# TRSW_and_RXamp_FINAL_mods.net
KiCad netlist of a schematic drawn in EAGLE
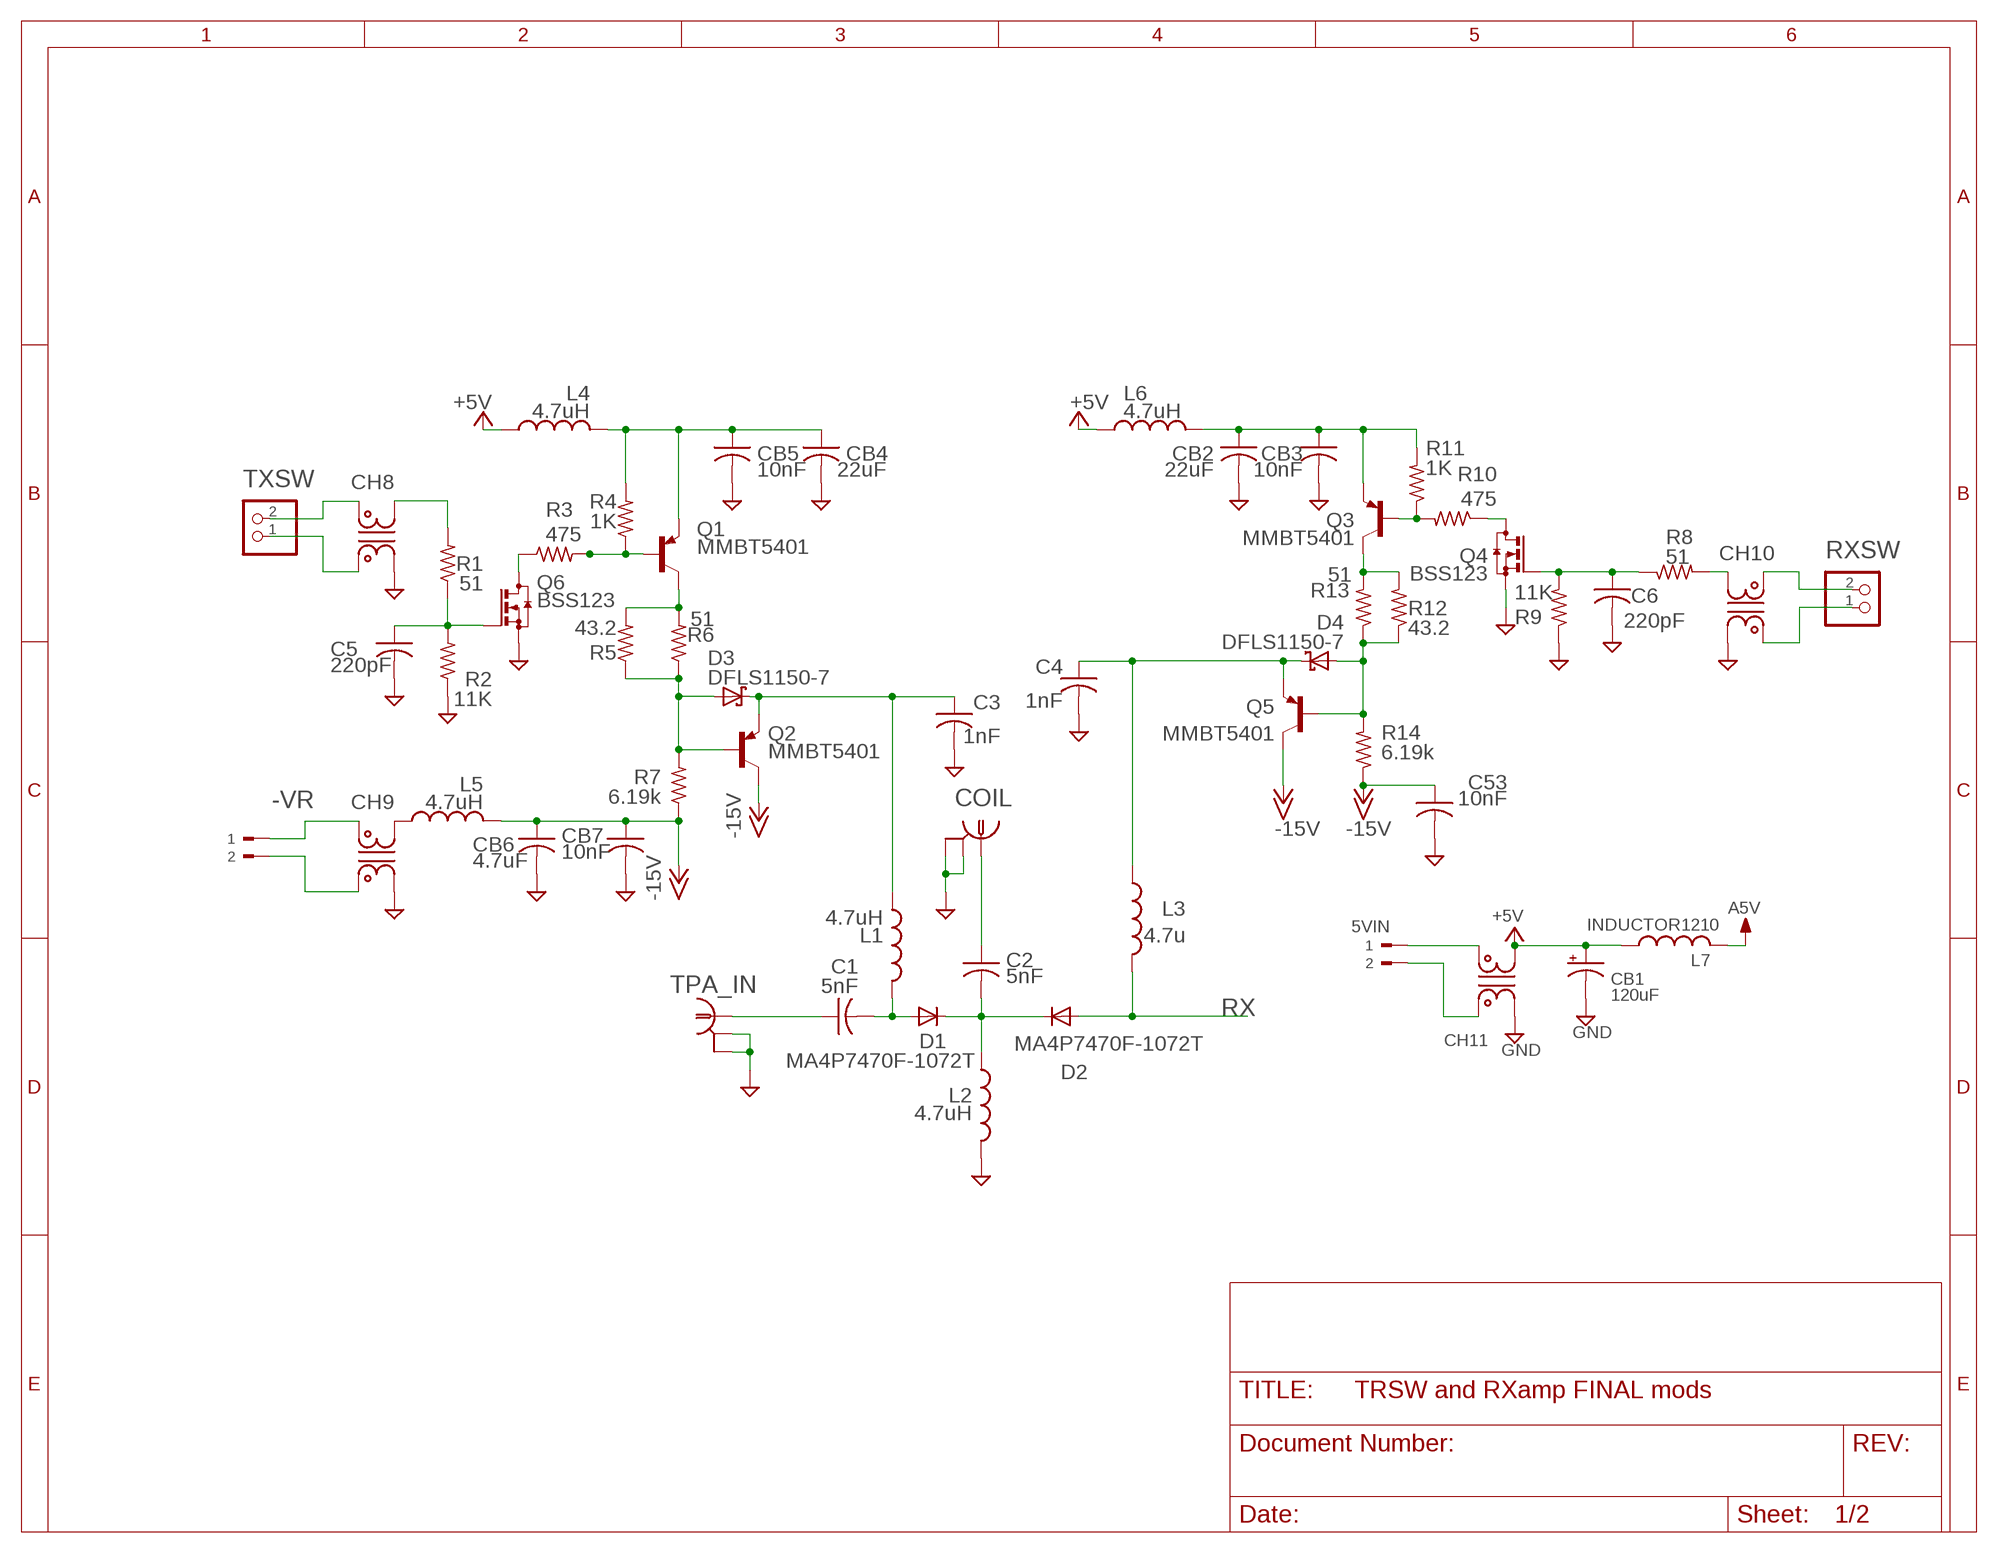
[diagram p0: schematic, sheet 1]
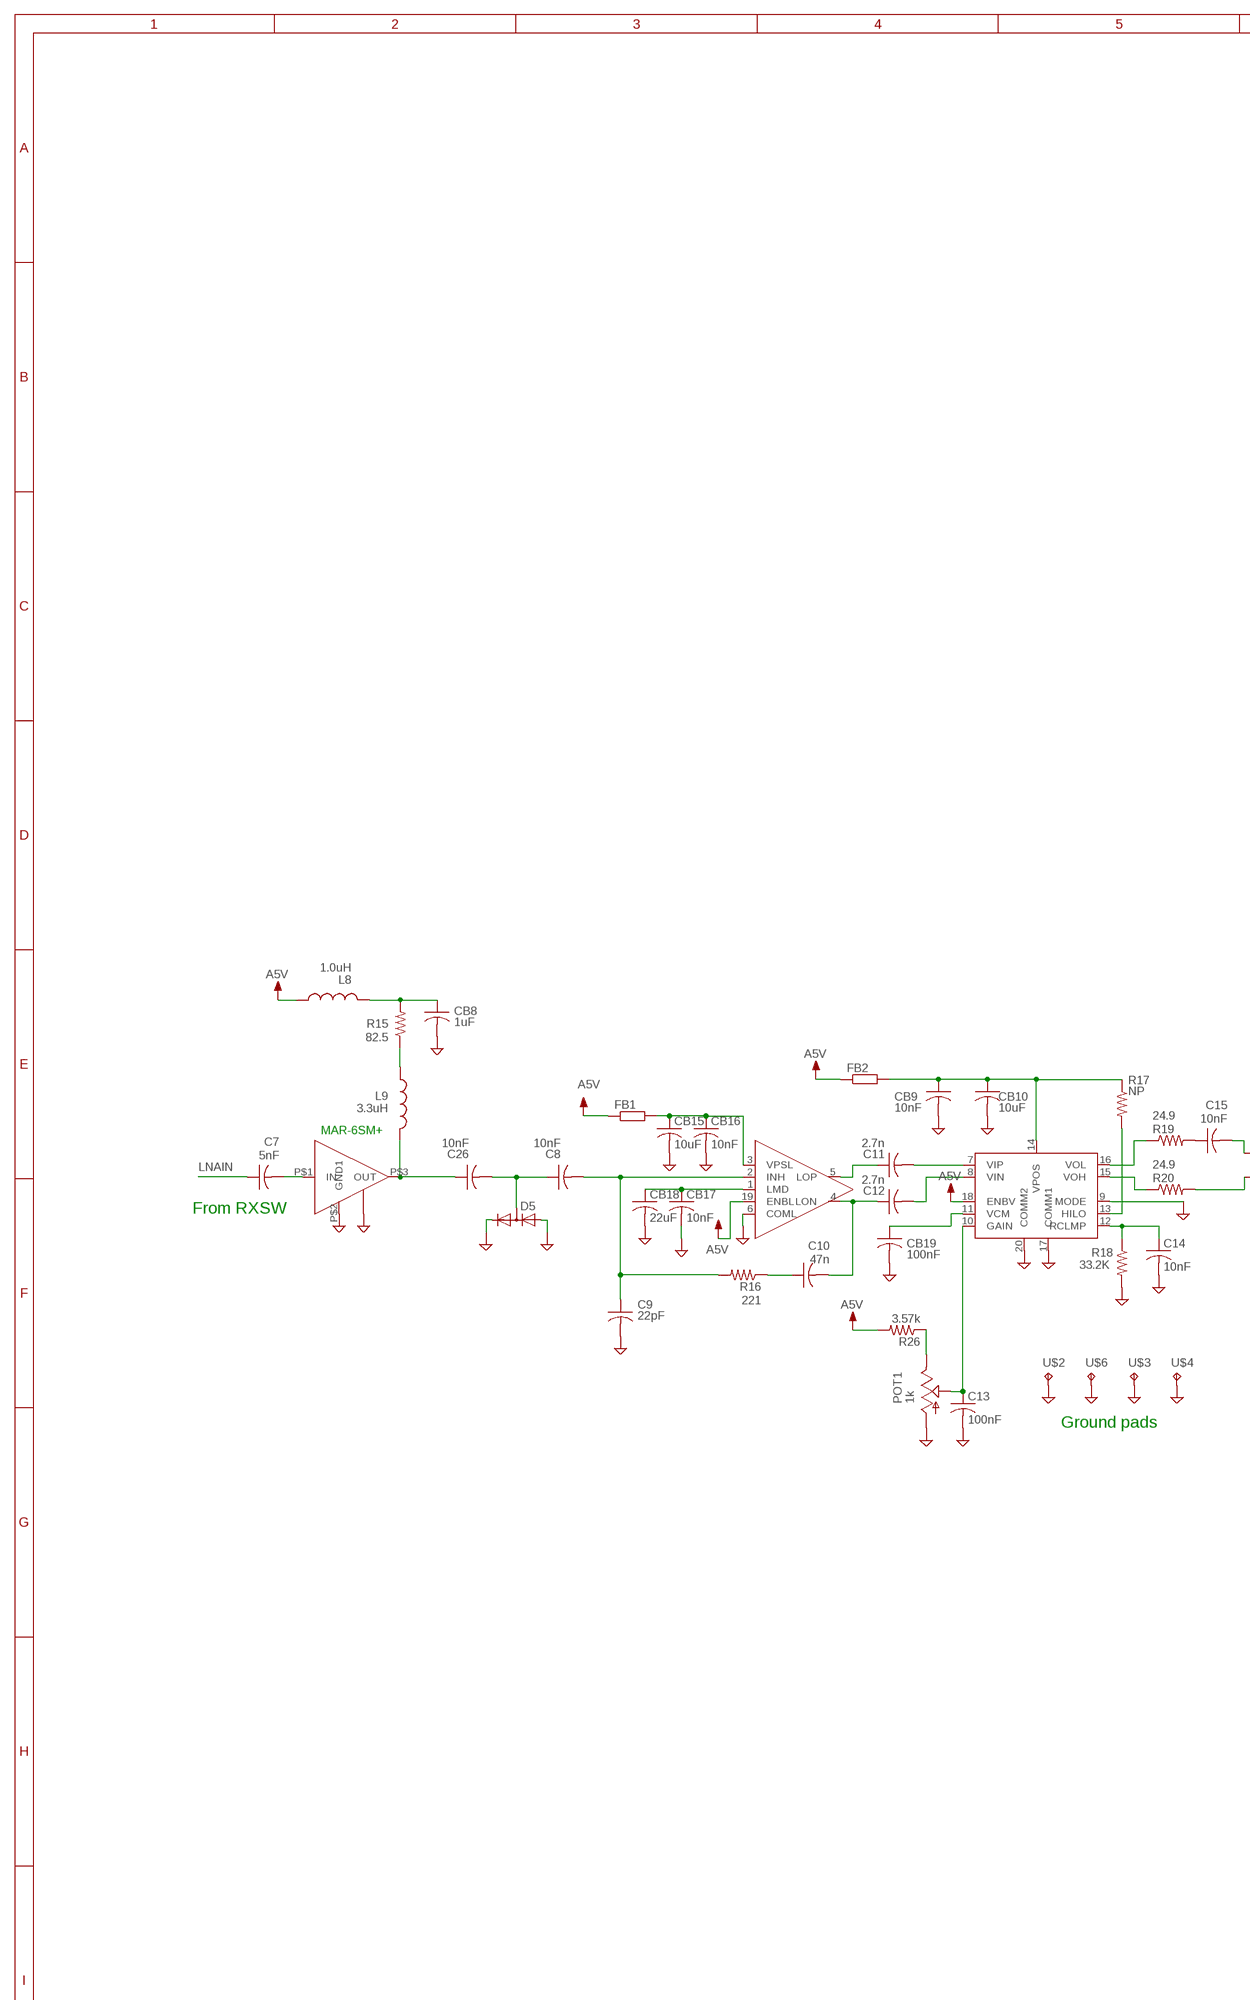
[diagram p1: schematic, sheet 2, part 1 of 2]
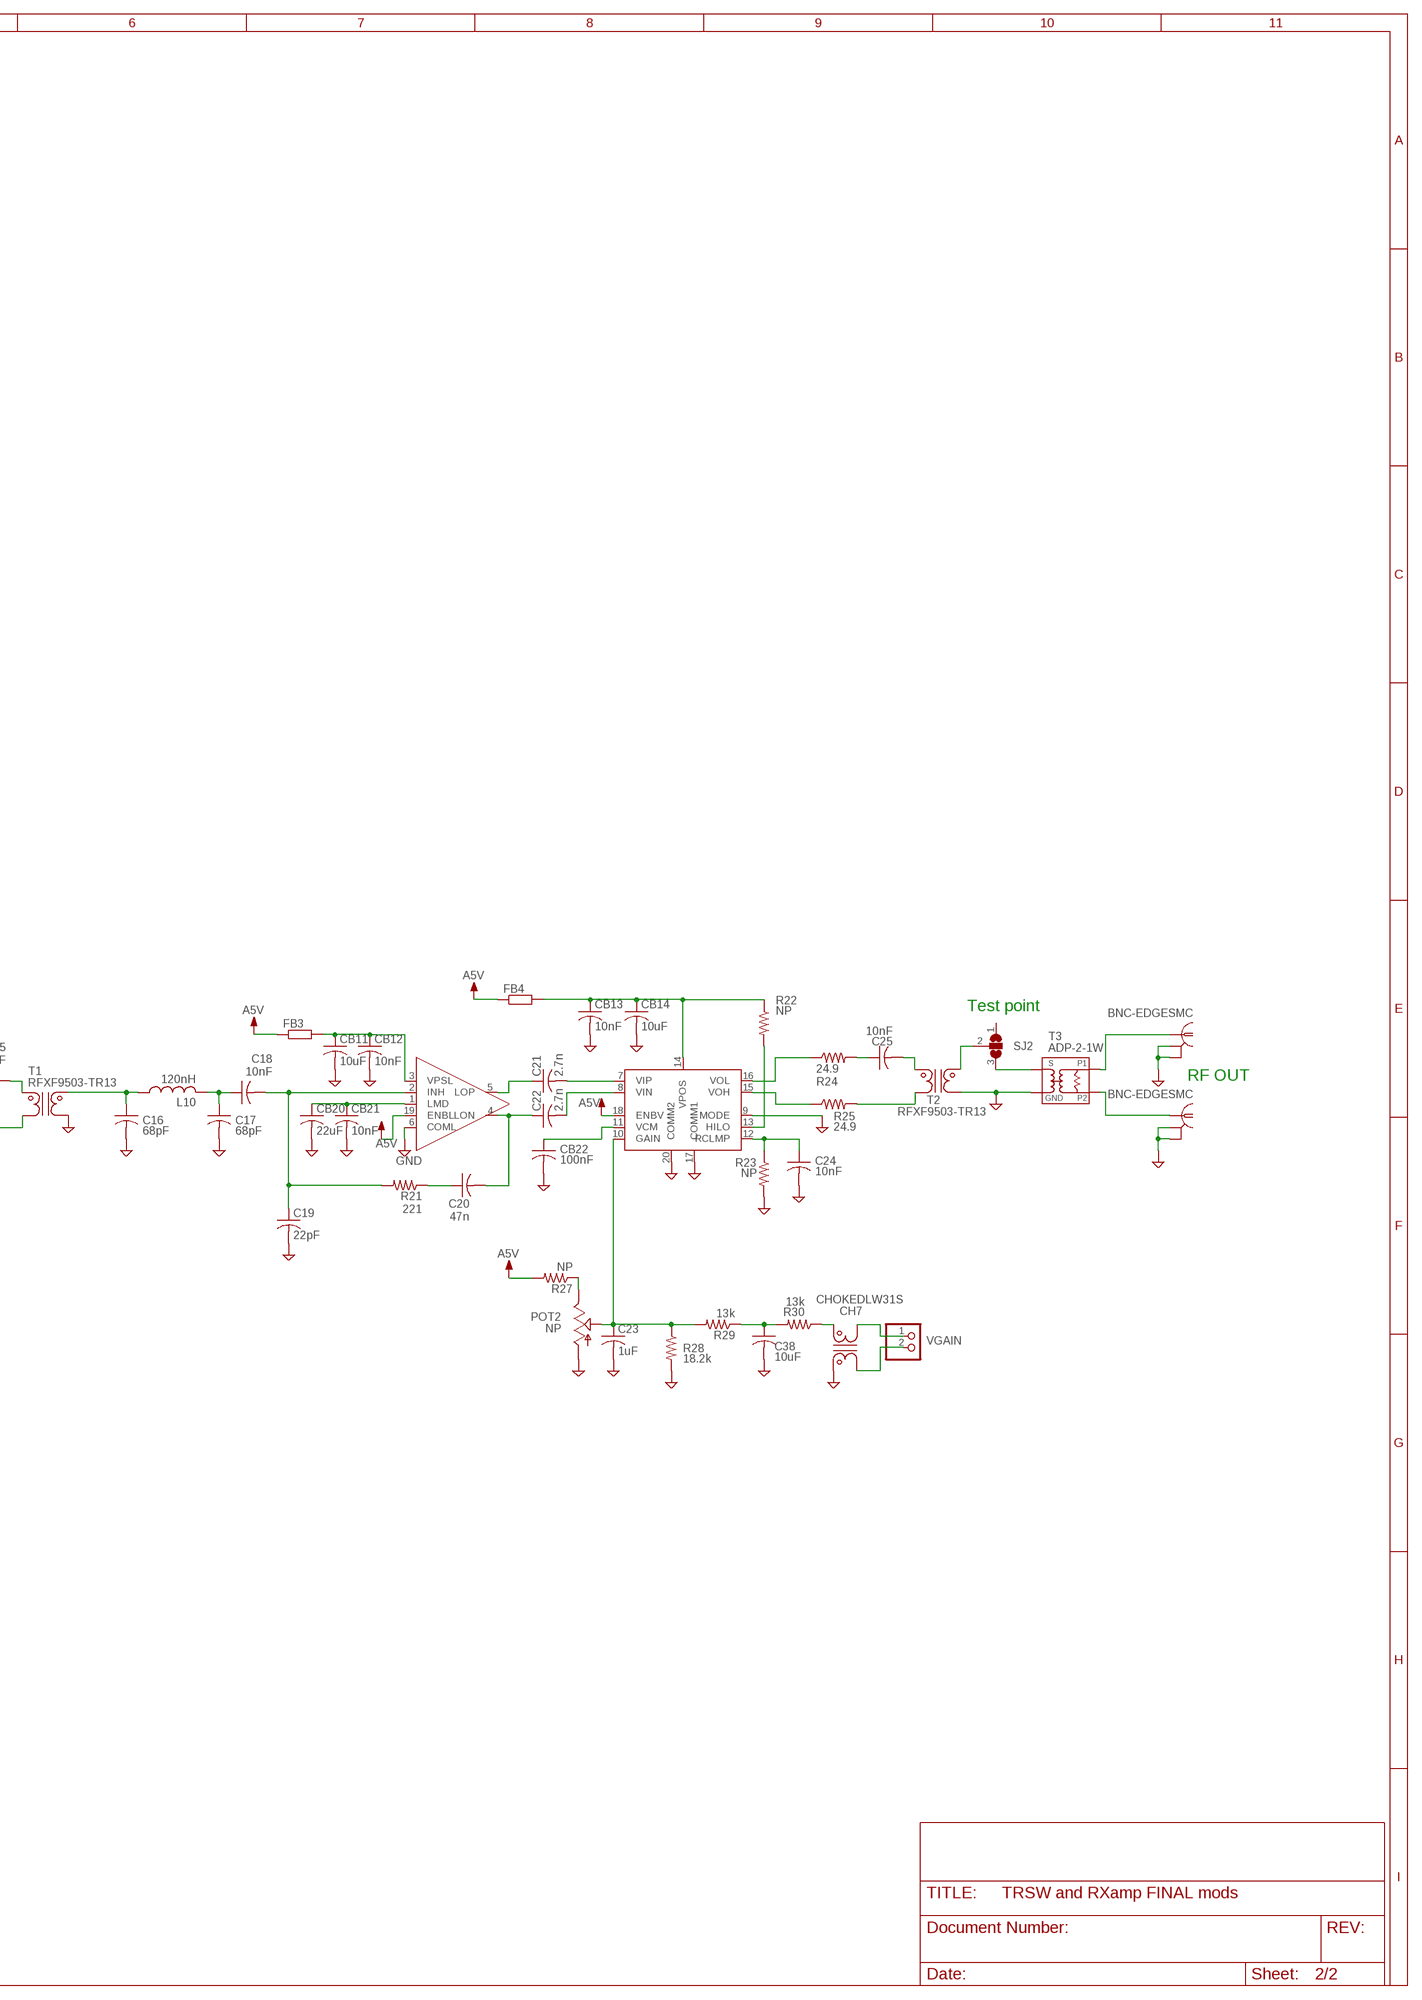
[diagram p2: schematic, sheet 2, part 2 of 2]

(export (version "E")
  (design (tool "Eeschema 10.0.6"))
  (components
    (comp (ref "C7")
      (value "5nF")
      (footprint "eagle-import:1008")
      (libsource (lib "eagle-import") (part "CAPACITOR1008"))
    )
    (comp (ref "C8")
      (value "10nF")
      (footprint "eagle-import:C0805")
      (libsource (lib "eagle-import") (part "C-USC0805"))
    )
    (comp (ref "C9")
      (value "22pF")
      (footprint "eagle-import:C0805")
      (libsource (lib "eagle-import") (part "C-USC0805"))
    )
    (comp (ref "C10")
      (value "47n")
      (footprint "eagle-import:C0805")
      (libsource (lib "eagle-import") (part "C-USC0805"))
    )
    (comp (ref "C11")
      (value "2.7n")
      (footprint "eagle-import:C0603")
      (libsource (lib "eagle-import") (part "C-USC0603"))
    )
    (comp (ref "C12")
      (value "2.7n")
      (footprint "eagle-import:C0603")
      (libsource (lib "eagle-import") (part "C-USC0603"))
    )
    (comp (ref "C13")
      (value "100nF")
      (footprint "eagle-import:C0603")
      (libsource (lib "eagle-import") (part "C-USC0603"))
    )
    (comp (ref "C14")
      (value "10nF")
      (footprint "eagle-import:C0603")
      (libsource (lib "eagle-import") (part "C-USC0603"))
    )
    (comp (ref "C15")
      (value "10nF")
      (footprint "eagle-import:C0603")
      (libsource (lib "eagle-import") (part "C-USC0603"))
    )
    (comp (ref "C16")
      (value "68pF")
      (footprint "eagle-import:1008")
      (libsource (lib "eagle-import") (part "CAPACITOR1008"))
    )
    (comp (ref "C17")
      (value "68pF")
      (footprint "eagle-import:1008")
      (libsource (lib "eagle-import") (part "CAPACITOR1008"))
    )
    (comp (ref "C18")
      (value "10nF")
      (footprint "eagle-import:C0805")
      (libsource (lib "eagle-import") (part "C-USC0805"))
    )
    (comp (ref "C19")
      (value "22pF")
      (footprint "eagle-import:C0805")
      (libsource (lib "eagle-import") (part "C-USC0805"))
    )
    (comp (ref "C20")
      (value "47n")
      (footprint "eagle-import:C0805")
      (libsource (lib "eagle-import") (part "C-USC0805"))
    )
    (comp (ref "C21")
      (value "2.7n")
      (footprint "eagle-import:C0603")
      (libsource (lib "eagle-import") (part "C-USC0603"))
    )
    (comp (ref "C22")
      (value "2.7n")
      (footprint "eagle-import:C0603")
      (libsource (lib "eagle-import") (part "C-USC0603"))
    )
    (comp (ref "C23")
      (value "1uF")
      (footprint "eagle-import:C0805")
      (libsource (lib "eagle-import") (part "C-USC0805"))
    )
    (comp (ref "C24")
      (value "10nF")
      (footprint "eagle-import:C0603")
      (libsource (lib "eagle-import") (part "C-USC0603"))
    )
    (comp (ref "C25")
      (value "10nF")
      (footprint "eagle-import:C0603")
      (libsource (lib "eagle-import") (part "C-USC0603"))
    )
    (comp (ref "C26")
      (value "10nF")
      (footprint "eagle-import:C0805")
      (libsource (lib "eagle-import") (part "C-USC0805"))
    )
    (comp (ref "C38")
      (value "10uF")
      (footprint "eagle-import:C0805")
      (libsource (lib "eagle-import") (part "C-USC0805"))
    )
    (comp (ref "CB8")
      (value "1uF")
      (footprint "eagle-import:C0805")
      (libsource (lib "eagle-import") (part "C-USC0805"))
    )
    (comp (ref "CB9")
      (value "10nF")
      (footprint "eagle-import:C0603")
      (libsource (lib "eagle-import") (part "C-USC0603"))
    )
    (comp (ref "CB10")
      (value "10uF")
      (footprint "eagle-import:C0805")
      (libsource (lib "eagle-import") (part "C-USC0805"))
    )
    (comp (ref "CB11")
      (value "10uF")
      (footprint "eagle-import:C0805")
      (libsource (lib "eagle-import") (part "C-USC0805"))
    )
    (comp (ref "CB12")
      (value "10nF")
      (footprint "eagle-import:C0603")
      (libsource (lib "eagle-import") (part "C-USC0603"))
    )
    (comp (ref "CB13")
      (value "10nF")
      (footprint "eagle-import:C0603")
      (libsource (lib "eagle-import") (part "C-USC0603"))
    )
    (comp (ref "CB14")
      (value "10uF")
      (footprint "eagle-import:C0805")
      (libsource (lib "eagle-import") (part "C-USC0805"))
    )
    (comp (ref "CB15")
      (value "10uF")
      (footprint "eagle-import:C0805")
      (libsource (lib "eagle-import") (part "C-USC0805"))
    )
    (comp (ref "CB16")
      (value "10nF")
      (footprint "eagle-import:C0603")
      (libsource (lib "eagle-import") (part "C-USC0603"))
    )
    (comp (ref "CB17")
      (value "10nF")
      (footprint "eagle-import:C0603")
      (libsource (lib "eagle-import") (part "C-USC0603"))
    )
    (comp (ref "CB18")
      (value "22uF")
      (footprint "eagle-import:C0805")
      (libsource (lib "eagle-import") (part "C-USC0805"))
    )
    (comp (ref "CB19")
      (value "100nF")
      (footprint "eagle-import:C0603")
      (libsource (lib "eagle-import") (part "C-USC0603"))
    )
    (comp (ref "CB20")
      (value "22uF")
      (footprint "eagle-import:C0805")
      (libsource (lib "eagle-import") (part "C-USC0805"))
    )
    (comp (ref "CB21")
      (value "10nF")
      (footprint "eagle-import:C0603")
      (libsource (lib "eagle-import") (part "C-USC0603"))
    )
    (comp (ref "CB22")
      (value "100nF")
      (footprint "eagle-import:C0603")
      (libsource (lib "eagle-import") (part "C-USC0603"))
    )
    (comp (ref "CH7")
      (value "CHOKEDLW31S")
      (footprint "eagle-import:CHOKE_DLW31S")
      (libsource (lib "eagle-import") (part "CHOKEDLW31S"))
    )
    (comp (ref "D5")
      (value "DIODE_2CACA-SOT23")
      (footprint "eagle-import:SOT23")
      (libsource (lib "eagle-import") (part "DIODE_2CACA-SOT23"))
    )
    (comp (ref "FB1")
      (value "R-EU_R0603")
      (footprint "eagle-import:R0603")
      (libsource (lib "eagle-import") (part "R-EU_R0603"))
    )
    (comp (ref "FB2")
      (value "R-EU_R0603")
      (footprint "eagle-import:R0603")
      (libsource (lib "eagle-import") (part "R-EU_R0603"))
    )
    (comp (ref "FB3")
      (value "R-EU_R0603")
      (footprint "eagle-import:R0603")
      (libsource (lib "eagle-import") (part "R-EU_R0603"))
    )
    (comp (ref "FB4")
      (value "R-EU_R0603")
      (footprint "eagle-import:R0603")
      (libsource (lib "eagle-import") (part "R-EU_R0603"))
    )
    (comp (ref "L8")
      (value "1.0uH")
      (footprint "eagle-import:1008")
      (libsource (lib "eagle-import") (part "INDUCTOR1008"))
    )
    (comp (ref "L9")
      (value "3.3uH")
      (footprint "eagle-import:1008")
      (libsource (lib "eagle-import") (part "INDUCTOR1008"))
    )
    (comp (ref "L10")
      (value "120nH")
      (footprint "eagle-import:1008")
      (libsource (lib "eagle-import") (part "INDUCTOR1008"))
    )
    (comp (ref "LNA")
      (value "MAR-6SM+")
      (footprint "eagle-import:WW107")
      (libsource (lib "eagle-import") (part "MAR-6SM+"))
    )
    (comp (ref "POT1")
      (value "1k")
      (footprint "eagle-import:3223W")
      (libsource (lib "eagle-import") (part "TRIM_US-3223W"))
    )
    (comp (ref "POT2")
      (value "NP")
      (footprint "eagle-import:3223W")
      (libsource (lib "eagle-import") (part "TRIM_US-3223W"))
    )
    (comp (ref "R15")
      (value "82.5")
      (footprint "eagle-import:R0805")
      (libsource (lib "eagle-import") (part "R-US_R0805"))
    )
    (comp (ref "R16")
      (value "221")
      (footprint "eagle-import:R0805")
      (libsource (lib "eagle-import") (part "R-US_R0805"))
    )
    (comp (ref "R17")
      (value "NP")
      (footprint "eagle-import:R0805")
      (libsource (lib "eagle-import") (part "R-US_R0805"))
    )
    (comp (ref "R18")
      (value "33.2K")
      (footprint "eagle-import:R0805")
      (libsource (lib "eagle-import") (part "R-US_R0805"))
    )
    (comp (ref "R19")
      (value "24.9")
      (footprint "eagle-import:R0805")
      (libsource (lib "eagle-import") (part "R-US_R0805"))
    )
    (comp (ref "R20")
      (value "24.9")
      (footprint "eagle-import:R0805")
      (libsource (lib "eagle-import") (part "R-US_R0805"))
    )
    (comp (ref "R21")
      (value "221")
      (footprint "eagle-import:R0805")
      (libsource (lib "eagle-import") (part "R-US_R0805"))
    )
    (comp (ref "R22")
      (value "NP")
      (footprint "eagle-import:R0805")
      (libsource (lib "eagle-import") (part "R-US_R0805"))
    )
    (comp (ref "R23")
      (value "NP")
      (footprint "eagle-import:R0805")
      (libsource (lib "eagle-import") (part "R-US_R0805"))
    )
    (comp (ref "R24")
      (value "24.9")
      (footprint "eagle-import:R0805")
      (libsource (lib "eagle-import") (part "R-US_R0805"))
    )
    (comp (ref "R25")
      (value "24.9")
      (footprint "eagle-import:R0805")
      (libsource (lib "eagle-import") (part "R-US_R0805"))
    )
    (comp (ref "R26")
      (value "3.57k")
      (footprint "eagle-import:R0805")
      (libsource (lib "eagle-import") (part "R-US_R0805"))
    )
    (comp (ref "R27")
      (value "NP")
      (footprint "eagle-import:R0805")
      (libsource (lib "eagle-import") (part "R-US_R0805"))
    )
    (comp (ref "R28")
      (value "18.2k")
      (footprint "eagle-import:R0805")
      (libsource (lib "eagle-import") (part "R-US_R0805"))
    )
    (comp (ref "R29")
      (value "13k")
      (footprint "eagle-import:R0805")
      (libsource (lib "eagle-import") (part "R-US_R0805"))
    )
    (comp (ref "R30")
      (value "13k")
      (footprint "eagle-import:R0805")
      (libsource (lib "eagle-import") (part "R-US_R0805"))
    )
    (comp (ref "RF_OUT")
      (value "BNC-EDGESMC")
      (footprint "eagle-import:SMC-EDGE")
      (libsource (lib "eagle-import") (part "BNC-EDGESMC"))
    )
    (comp (ref "SJ2")
      (value "SJ2W")
      (footprint "eagle-import:SJ_2")
      (libsource (lib "eagle-import") (part "SJ2W"))
    )
    (comp (ref "T1")
      (value "RFXF9503-TR13")
      (footprint "eagle-import:CX20XX_BALUN")
      (libsource (lib "eagle-import") (part "BALUN_1{colon}1"))
    )
    (comp (ref "T2")
      (value "RFXF9503-TR13")
      (footprint "eagle-import:CX20XX_BALUN")
      (libsource (lib "eagle-import") (part "BALUN_1{colon}1"))
    )
    (comp (ref "T3")
      (value "ADP-2-1W")
      (footprint "eagle-import:CD636")
      (libsource (lib "eagle-import") (part "ADP-2-1W"))
    )
    (comp (ref "U$2")
      (value "TESTPOINTKEYSTONE_ELECTRONICS_5016")
      (footprint "eagle-import:SMD_TESTPAD")
      (libsource (lib "eagle-import") (part "TESTPOINTKEYSTONE_ELECTRONICS_5016"))
    )
    (comp (ref "U$3")
      (value "TESTPOINTKEYSTONE_ELECTRONICS_5016")
      (footprint "eagle-import:SMD_TESTPAD")
      (libsource (lib "eagle-import") (part "TESTPOINTKEYSTONE_ELECTRONICS_5016"))
    )
    (comp (ref "U$4")
      (value "TESTPOINTKEYSTONE_ELECTRONICS_5016")
      (footprint "eagle-import:SMD_TESTPAD")
      (libsource (lib "eagle-import") (part "TESTPOINTKEYSTONE_ELECTRONICS_5016"))
    )
    (comp (ref "U$6")
      (value "SOLDERPADSMALL")
      (footprint "eagle-import:PAD-SMALL")
      (libsource (lib "eagle-import") (part "SOLDERPADSMALL"))
    )
    (comp (ref "U$27")
      (value "BNC-EDGESMC")
      (footprint "eagle-import:SMC-EDGE")
      (libsource (lib "eagle-import") (part "BNC-EDGESMC"))
    )
    (comp (ref "U1")
      (value "AD8331")
      (footprint "eagle-import:QSOP-20")
      (libsource (lib "eagle-import") (part "AD8331"))
    )
    (comp (ref "U2")
      (value "AD8331")
      (footprint "eagle-import:QSOP-20")
      (libsource (lib "eagle-import") (part "AD8331"))
    )
    (comp (ref "VGAIN")
      (value "PINHD-1X2")
      (footprint "eagle-import:1X02")
      (libsource (lib "eagle-import") (part "PINHD-1X2"))
    )
    (comp (ref "-VR")
      (value "TERM-2OMNIMATE_SL")
      (footprint "eagle-import:OMNIMATE_SL_2POS")
      (libsource (lib "eagle-import") (part "TERM-2OMNIMATE_SL"))
    )
    (comp (ref "5VIN")
      (value "TERM-2OMNIMATE_SL")
      (footprint "eagle-import:OMNIMATE_SL_2POS")
      (libsource (lib "eagle-import") (part "TERM-2OMNIMATE_SL"))
    )
    (comp (ref "C1")
      (value "5nF")
      (footprint "eagle-import:1008")
      (libsource (lib "eagle-import") (part "CAPACITOR1008"))
    )
    (comp (ref "C2")
      (value "5nF")
      (footprint "eagle-import:1008")
      (libsource (lib "eagle-import") (part "CAPACITOR1008"))
    )
    (comp (ref "C3")
      (value "1nF")
      (footprint "eagle-import:C0805")
      (libsource (lib "eagle-import") (part "C-USC0805"))
    )
    (comp (ref "C4")
      (value "1nF")
      (footprint "eagle-import:C0805")
      (libsource (lib "eagle-import") (part "C-USC0805"))
    )
    (comp (ref "C5")
      (value "220pF")
      (footprint "eagle-import:C0805")
      (libsource (lib "eagle-import") (part "C-USC0805"))
    )
    (comp (ref "C6")
      (value "220pF")
      (footprint "eagle-import:C0805")
      (libsource (lib "eagle-import") (part "C-USC0805"))
    )
    (comp (ref "C53")
      (value "10nF")
      (footprint "eagle-import:C0603")
      (libsource (lib "eagle-import") (part "C-USC0603"))
    )
    (comp (ref "CB1")
      (value "120uF")
      (footprint "eagle-import:E3,5-8")
      (libsource (lib "eagle-import") (part "CPOL-USE3.5-8"))
    )
    (comp (ref "CB2")
      (value "22uF")
      (footprint "eagle-import:C0805")
      (libsource (lib "eagle-import") (part "C-USC0805"))
    )
    (comp (ref "CB3")
      (value "10nF")
      (footprint "eagle-import:C0603")
      (libsource (lib "eagle-import") (part "C-USC0603"))
    )
    (comp (ref "CB4")
      (value "22uF")
      (footprint "eagle-import:C0805")
      (libsource (lib "eagle-import") (part "C-USC0805"))
    )
    (comp (ref "CB5")
      (value "10nF")
      (footprint "eagle-import:C0603")
      (libsource (lib "eagle-import") (part "C-USC0603"))
    )
    (comp (ref "CB6")
      (value "4.7uF")
      (footprint "eagle-import:C0805")
      (libsource (lib "eagle-import") (part "C-USC0805"))
    )
    (comp (ref "CB7")
      (value "10nF")
      (footprint "eagle-import:C0603")
      (libsource (lib "eagle-import") (part "C-USC0603"))
    )
    (comp (ref "CH8")
      (value "CHOKEDLW31S")
      (footprint "eagle-import:CHOKE_DLW31S")
      (libsource (lib "eagle-import") (part "CHOKEDLW31S"))
    )
    (comp (ref "CH9")
      (value "CHOKE")
      (footprint "eagle-import:CHOKE_DLW5BT")
      (libsource (lib "eagle-import") (part "CHOKE"))
    )
    (comp (ref "CH10")
      (value "CHOKEDLW31S")
      (footprint "eagle-import:CHOKE_DLW31S")
      (libsource (lib "eagle-import") (part "CHOKEDLW31S"))
    )
    (comp (ref "CH11")
      (value "CHOKE")
      (footprint "eagle-import:CHOKE_DLW5BT")
      (libsource (lib "eagle-import") (part "CHOKE"))
    )
    (comp (ref "COIL")
      (value "BNC-EDGE")
      (footprint "eagle-import:BNC-EDGE")
      (libsource (lib "eagle-import") (part "BNC-EDGE"))
    )
    (comp (ref "D1")
      (value "MA4P7470F-1072T")
      (footprint "eagle-import:1210-POLAR")
      (libsource (lib "eagle-import") (part "DIODE"))
    )
    (comp (ref "D2")
      (value "MA4P7470F-1072T")
      (footprint "eagle-import:1210-POLAR")
      (libsource (lib "eagle-import") (part "DIODE"))
    )
    (comp (ref "D3")
      (value "DFLS1150-7")
      (footprint "eagle-import:POWERDI-123")
      (libsource (lib "eagle-import") (part "DIODE-SCHOTTKYPOWERDI-123"))
    )
    (comp (ref "D4")
      (value "DFLS1150-7")
      (footprint "eagle-import:POWERDI-123")
      (libsource (lib "eagle-import") (part "DIODE-SCHOTTKYPOWERDI-123"))
    )
    (comp (ref "L1")
      (value "4.7uH")
      (footprint "eagle-import:1210")
      (libsource (lib "eagle-import") (part "INDUCTOR1210"))
    )
    (comp (ref "L2")
      (value "4.7uH")
      (footprint "eagle-import:1210")
      (libsource (lib "eagle-import") (part "INDUCTOR1210"))
    )
    (comp (ref "L3")
      (value "4.7u")
      (footprint "eagle-import:1210")
      (libsource (lib "eagle-import") (part "INDUCTOR1210"))
    )
    (comp (ref "L4")
      (value "4.7uH")
      (footprint "eagle-import:1210")
      (libsource (lib "eagle-import") (part "INDUCTOR1210"))
    )
    (comp (ref "L5")
      (value "4.7uH")
      (footprint "eagle-import:1210")
      (libsource (lib "eagle-import") (part "INDUCTOR1210"))
    )
    (comp (ref "L6")
      (value "4.7uH")
      (footprint "eagle-import:1210")
      (libsource (lib "eagle-import") (part "INDUCTOR1210"))
    )
    (comp (ref "L7")
      (value "INDUCTOR1210")
      (footprint "eagle-import:1210")
      (libsource (lib "eagle-import") (part "INDUCTOR1210"))
    )
    (comp (ref "Q1")
      (value "MMBT5401")
      (footprint "eagle-import:SOT23-BEC")
      (libsource (lib "eagle-import") (part "BF821SMD"))
    )
    (comp (ref "Q2")
      (value "MMBT5401")
      (footprint "eagle-import:SOT23-BEC")
      (libsource (lib "eagle-import") (part "BF821SMD"))
    )
    (comp (ref "Q3")
      (value "MMBT5401")
      (footprint "eagle-import:SOT23-BEC")
      (libsource (lib "eagle-import") (part "BF821SMD"))
    )
    (comp (ref "Q4")
      (value "BSS123")
      (footprint "eagle-import:SOT23")
      (libsource (lib "eagle-import") (part "BSS123"))
    )
    (comp (ref "Q5")
      (value "MMBT5401")
      (footprint "eagle-import:SOT23-BEC")
      (libsource (lib "eagle-import") (part "BF821SMD"))
    )
    (comp (ref "Q6")
      (value "BSS123")
      (footprint "eagle-import:SOT23")
      (libsource (lib "eagle-import") (part "BSS123"))
    )
    (comp (ref "R1")
      (value "51")
      (footprint "eagle-import:R0805")
      (libsource (lib "eagle-import") (part "R-US_R0805"))
    )
    (comp (ref "R2")
      (value "11K")
      (footprint "eagle-import:R0805")
      (libsource (lib "eagle-import") (part "R-US_R0805"))
    )
    (comp (ref "R3")
      (value "475")
      (footprint "eagle-import:R0805")
      (libsource (lib "eagle-import") (part "R-US_R0805"))
    )
    (comp (ref "R4")
      (value "1K")
      (footprint "eagle-import:R0805")
      (libsource (lib "eagle-import") (part "R-US_R0805"))
    )
    (comp (ref "R5")
      (value "43.2")
      (footprint "eagle-import:R0805")
      (libsource (lib "eagle-import") (part "R-US_R0805"))
    )
    (comp (ref "R6")
      (value "51")
      (footprint "eagle-import:R0805")
      (libsource (lib "eagle-import") (part "R-US_R0805"))
    )
    (comp (ref "R7")
      (value "6.19k")
      (footprint "eagle-import:R0805")
      (libsource (lib "eagle-import") (part "R-US_R0805"))
    )
    (comp (ref "R8")
      (value "51")
      (footprint "eagle-import:R0805")
      (libsource (lib "eagle-import") (part "R-US_R0805"))
    )
    (comp (ref "R9")
      (value "11K")
      (footprint "eagle-import:R0805")
      (libsource (lib "eagle-import") (part "R-US_R0805"))
    )
    (comp (ref "R10")
      (value "475")
      (footprint "eagle-import:R0805")
      (libsource (lib "eagle-import") (part "R-US_R0805"))
    )
    (comp (ref "R11")
      (value "1K")
      (footprint "eagle-import:R0805")
      (libsource (lib "eagle-import") (part "R-US_R0805"))
    )
    (comp (ref "R12")
      (value "43.2")
      (footprint "eagle-import:R0805")
      (libsource (lib "eagle-import") (part "R-US_R0805"))
    )
    (comp (ref "R13")
      (value "51")
      (footprint "eagle-import:R0805")
      (libsource (lib "eagle-import") (part "R-US_R0805"))
    )
    (comp (ref "R14")
      (value "6.19k")
      (footprint "eagle-import:R0805")
      (libsource (lib "eagle-import") (part "R-US_R0805"))
    )
    (comp (ref "RXSW")
      (value "PINHD-1X2")
      (footprint "eagle-import:1X02")
      (libsource (lib "eagle-import") (part "PINHD-1X2"))
    )
    (comp (ref "TPA_IN")
      (value "BNC-EDGE")
      (footprint "eagle-import:BNC-EDGE")
      (libsource (lib "eagle-import") (part "BNC-EDGE"))
    )
    (comp (ref "TXSW")
      (value "PINHD-1X2")
      (footprint "eagle-import:1X02")
      (libsource (lib "eagle-import") (part "PINHD-1X2"))
    )
  )
  (nets
    (net (code "1") (name "+5V") (class "Default")
      (node (ref "CB1") (pin "+") (pinfunction "+_+") (pintype "passive"))
      (node (ref "CH11") (pin "P$3") (pinfunction "3_P$3") (pintype "passive"))
      (node (ref "L4") (pin "1") (pinfunction "1_1") (pintype "passive"))
      (node (ref "L6") (pin "2") (pinfunction "2_2") (pintype "passive"))
      (node (ref "L7") (pin "1") (pinfunction "1_1") (pintype "passive"))
    )
    (net (code "2") (name "-15V") (class "Default")
      (node (ref "C53") (pin "1") (pinfunction "1_1") (pintype "passive"))
      (node (ref "CB6") (pin "1") (pinfunction "1_1") (pintype "passive"))
      (node (ref "CB7") (pin "1") (pinfunction "1_1") (pintype "passive"))
      (node (ref "L5") (pin "2") (pinfunction "2_2") (pintype "passive"))
      (node (ref "Q2") (pin "C") (pinfunction "C_C") (pintype "passive"))
      (node (ref "Q5") (pin "C") (pinfunction "C_C") (pintype "passive"))
      (node (ref "R14") (pin "1") (pinfunction "1_1") (pintype "passive"))
      (node (ref "R7") (pin "1") (pinfunction "1_1") (pintype "passive"))
    )
    (net (code "3") (name "A5V") (class "Default")
      (node (ref "FB1") (pin "1") (pinfunction "1_1") (pintype "passive"))
      (node (ref "FB2") (pin "1") (pinfunction "1_1") (pintype "passive"))
      (node (ref "FB3") (pin "1") (pinfunction "1_1") (pintype "passive"))
      (node (ref "FB4") (pin "1") (pinfunction "1_1") (pintype "passive"))
      (node (ref "L7") (pin "2") (pinfunction "2_2") (pintype "passive"))
      (node (ref "L8") (pin "P$1") (pinfunction "1_P$1") (pintype "passive"))
      (node (ref "R26") (pin "2") (pinfunction "2_2") (pintype "passive"))
      (node (ref "R27") (pin "2") (pinfunction "2_2") (pintype "passive"))
      (node (ref "U1") (pin "18") (pinfunction "ENBV_18") (pintype "input"))
      (node (ref "U1") (pin "19") (pinfunction "ENBL_19") (pintype "input"))
      (node (ref "U2") (pin "18") (pinfunction "ENBV_18") (pintype "input"))
      (node (ref "U2") (pin "19") (pinfunction "ENBL_19") (pintype "input"))
    )
    (net (code "4") (name "GND") (class "Default")
      (node (ref "C13") (pin "2") (pinfunction "2_2") (pintype "passive"))
      (node (ref "C14") (pin "2") (pinfunction "2_2") (pintype "passive"))
      (node (ref "C16") (pin "P$2") (pinfunction "2_P$2") (pintype "passive"))
      (node (ref "C17") (pin "P$2") (pinfunction "2_P$2") (pintype "passive"))
      (node (ref "C19") (pin "2") (pinfunction "2_2") (pintype "passive"))
      (node (ref "C23") (pin "2") (pinfunction "2_2") (pintype "passive"))
      (node (ref "C24") (pin "2") (pinfunction "2_2") (pintype "passive"))
      (node (ref "C3") (pin "2") (pinfunction "2_2") (pintype "passive"))
      (node (ref "C38") (pin "2") (pinfunction "2_2") (pintype "passive"))
      (node (ref "C4") (pin "2") (pinfunction "2_2") (pintype "passive"))
      (node (ref "C5") (pin "2") (pinfunction "2_2") (pintype "passive"))
      (node (ref "C53") (pin "2") (pinfunction "2_2") (pintype "passive"))
      (node (ref "C6") (pin "2") (pinfunction "2_2") (pintype "passive"))
      (node (ref "C9") (pin "2") (pinfunction "2_2") (pintype "passive"))
      (node (ref "CB1") (pin "-") (pinfunction "-_-") (pintype "passive"))
      (node (ref "CB10") (pin "2") (pinfunction "2_2") (pintype "passive"))
      (node (ref "CB11") (pin "2") (pinfunction "2_2") (pintype "passive"))
      (node (ref "CB12") (pin "2") (pinfunction "2_2") (pintype "passive"))
      (node (ref "CB13") (pin "2") (pinfunction "2_2") (pintype "passive"))
      (node (ref "CB14") (pin "2") (pinfunction "2_2") (pintype "passive"))
      (node (ref "CB15") (pin "2") (pinfunction "2_2") (pintype "passive"))
      (node (ref "CB16") (pin "2") (pinfunction "2_2") (pintype "passive"))
      (node (ref "CB17") (pin "2") (pinfunction "2_2") (pintype "passive"))
      (node (ref "CB18") (pin "2") (pinfunction "2_2") (pintype "passive"))
      (node (ref "CB19") (pin "2") (pinfunction "2_2") (pintype "passive"))
      (node (ref "CB2") (pin "2") (pinfunction "2_2") (pintype "passive"))
      (node (ref "CB20") (pin "2") (pinfunction "2_2") (pintype "passive"))
      (node (ref "CB21") (pin "2") (pinfunction "2_2") (pintype "passive"))
      (node (ref "CB22") (pin "2") (pinfunction "2_2") (pintype "passive"))
      (node (ref "CB3") (pin "2") (pinfunction "2_2") (pintype "passive"))
      (node (ref "CB4") (pin "2") (pinfunction "2_2") (pintype "passive"))
      (node (ref "CB5") (pin "2") (pinfunction "2_2") (pintype "passive"))
      (node (ref "CB6") (pin "2") (pinfunction "2_2") (pintype "passive"))
      (node (ref "CB7") (pin "2") (pinfunction "2_2") (pintype "passive"))
      (node (ref "CB8") (pin "2") (pinfunction "2_2") (pintype "passive"))
      (node (ref "CB9") (pin "2") (pinfunction "2_2") (pintype "passive"))
      (node (ref "CH10") (pin "P$2") (pinfunction "2_P$2") (pintype "passive"))
      (node (ref "CH11") (pin "P$2") (pinfunction "2_P$2") (pintype "passive"))
      (node (ref "CH7") (pin "P$1") (pinfunction "1_P$1") (pintype "passive"))
      (node (ref "CH8") (pin "P$2") (pinfunction "2_P$2") (pintype "passive"))
      (node (ref "CH9") (pin "P$2") (pinfunction "2_P$2") (pintype "passive"))
      (node (ref "COIL") (pin "S1") (pinfunction "GND1_S1") (pintype "power_in"))
      (node (ref "COIL") (pin "S2") (pinfunction "GND2_S2") (pintype "power_in"))
      (node (ref "D5") (pin "1") (pinfunction "A_1") (pintype "passive"))
      (node (ref "D5") (pin "2") (pinfunction "C_2") (pintype "passive"))
      (node (ref "L2") (pin "2") (pinfunction "2_2") (pintype "passive"))
      (node (ref "LNA") (pin "P$2") (pinfunction "GND1_P$2") (pintype "power_in"))
      (node (ref "LNA") (pin "P$4") (pinfunction "GND2_P$4") (pintype "power_in"))
      (node (ref "POT1") (pin "1") (pinfunction "A_1") (pintype "passive"))
      (node (ref "POT2") (pin "1") (pinfunction "A_1") (pintype "passive"))
      (node (ref "Q4") (pin "2") (pinfunction "S_2") (pintype "passive"))
      (node (ref "Q6") (pin "2") (pinfunction "S_2") (pintype "passive"))
      (node (ref "R18") (pin "2") (pinfunction "2_2") (pintype "passive"))
      (node (ref "R2") (pin "1") (pinfunction "1_1") (pintype "passive"))
      (node (ref "R23") (pin "2") (pinfunction "2_2") (pintype "passive"))
      (node (ref "R28") (pin "2") (pinfunction "2_2") (pintype "passive"))
      (node (ref "R9") (pin "1") (pinfunction "1_1") (pintype "passive"))
      (node (ref "RF_OUT") (pin "2") (pinfunction "GND1_2") (pintype "power_in"))
      (node (ref "RF_OUT") (pin "3") (pinfunction "GND2_3") (pintype "power_in"))
      (node (ref "T1") (pin "P$3") (pinfunction "3_P$3") (pintype "passive"))
      (node (ref "T2") (pin "P$3") (pinfunction "3_P$3") (pintype "passive"))
      (node (ref "T3") (pin "P$6") (pinfunction "GND_P$6") (pintype "passive"))
      (node (ref "TPA_IN") (pin "S1") (pinfunction "GND1_S1") (pintype "power_in"))
      (node (ref "TPA_IN") (pin "S2") (pinfunction "GND2_S2") (pintype "power_in"))
      (node (ref "U$2") (pin "P$1") (pinfunction "TP_P$1") (pintype "input"))
      (node (ref "U$27") (pin "2") (pinfunction "GND1_2") (pintype "power_in"))
      (node (ref "U$27") (pin "3") (pinfunction "GND2_3") (pintype "power_in"))
      (node (ref "U$3") (pin "P$1") (pinfunction "TP_P$1") (pintype "input"))
      (node (ref "U$4") (pin "P$1") (pinfunction "TP_P$1") (pintype "input"))
      (node (ref "U$6") (pin "P$1") (pinfunction "TP_P$1") (pintype "input"))
      (node (ref "U1") (pin "17") (pinfunction "COMM1_17") (pintype "power_in"))
      (node (ref "U1") (pin "20") (pinfunction "COMM2_20") (pintype "power_in"))
      (node (ref "U1") (pin "6") (pinfunction "COML_6") (pintype "power_in"))
      (node (ref "U1") (pin "9") (pinfunction "MODE_9") (pintype "input"))
      (node (ref "U2") (pin "17") (pinfunction "COMM1_17") (pintype "power_in"))
      (node (ref "U2") (pin "20") (pinfunction "COMM2_20") (pintype "power_in"))
      (node (ref "U2") (pin "6") (pinfunction "COML_6") (pintype "power_in"))
      (node (ref "U2") (pin "9") (pinfunction "MODE_9") (pintype "input"))
    )
    (net (code "5") (name "LNAIN") (class "Default")
      (node (ref "C7") (pin "P$1") (pinfunction "1_P$1") (pintype "passive"))
      (node (ref "D2") (pin "A") (pinfunction "A_A") (pintype "passive"))
      (node (ref "L3") (pin "2") (pinfunction "2_2") (pintype "passive"))
    )
    (net (code "6") (name "Net-(C1-1)") (class "Default")
      (node (ref "C1") (pin "P$1") (pinfunction "1_P$1") (pintype "passive"))
      (node (ref "TPA_IN") (pin "I") (pinfunction "1_I") (pintype "passive"))
    )
    (net (code "7") (name "Net-(C1-2)") (class "Default")
      (node (ref "C1") (pin "P$2") (pinfunction "2_P$2") (pintype "passive"))
      (node (ref "D1") (pin "A") (pinfunction "A_A") (pintype "passive"))
      (node (ref "L1") (pin "2") (pinfunction "2_2") (pintype "passive"))
    )
    (net (code "8") (name "Net-(C2-1)") (class "Default")
      (node (ref "C2") (pin "P$1") (pinfunction "1_P$1") (pintype "passive"))
      (node (ref "COIL") (pin "I") (pinfunction "1_I") (pintype "passive"))
    )
    (net (code "9") (name "Net-(C2-2)") (class "Default")
      (node (ref "C2") (pin "P$2") (pinfunction "2_P$2") (pintype "passive"))
      (node (ref "D1") (pin "K") (pinfunction "C_K") (pintype "passive"))
      (node (ref "D2") (pin "K") (pinfunction "C_K") (pintype "passive"))
      (node (ref "L2") (pin "1") (pinfunction "1_1") (pintype "passive"))
    )
    (net (code "10") (name "Net-(C7-2)") (class "Default")
      (node (ref "C7") (pin "P$2") (pinfunction "2_P$2") (pintype "passive"))
      (node (ref "LNA") (pin "P$1") (pinfunction "IN_P$1") (pintype "input"))
    )
    (net (code "11") (name "Net-(C10-Pad1)") (class "Default")
      (node (ref "C10") (pin "1") (pinfunction "1_1") (pintype "passive"))
      (node (ref "R16") (pin "1") (pinfunction "1_1") (pintype "passive"))
    )
    (net (code "12") (name "Net-(C15-Pad1)") (class "Default")
      (node (ref "C15") (pin "1") (pinfunction "1_1") (pintype "passive"))
      (node (ref "R19") (pin "2") (pinfunction "2_2") (pintype "passive"))
    )
    (net (code "13") (name "Net-(C16-1)") (class "Default")
      (node (ref "C16") (pin "P$1") (pinfunction "1_P$1") (pintype "passive"))
      (node (ref "L10") (pin "P$1") (pinfunction "1_P$1") (pintype "passive"))
      (node (ref "T1") (pin "P$4") (pinfunction "4_P$4") (pintype "passive"))
    )
    (net (code "14") (name "Net-(C17-1)") (class "Default")
      (node (ref "C17") (pin "P$1") (pinfunction "1_P$1") (pintype "passive"))
      (node (ref "C18") (pin "1") (pinfunction "1_1") (pintype "passive"))
      (node (ref "L10") (pin "P$2") (pinfunction "2_P$2") (pintype "passive"))
    )
    (net (code "15") (name "Net-(C20-Pad1)") (class "Default")
      (node (ref "C20") (pin "1") (pinfunction "1_1") (pintype "passive"))
      (node (ref "R21") (pin "1") (pinfunction "1_1") (pintype "passive"))
    )
    (net (code "16") (name "Net-(C25-Pad1)") (class "Default")
      (node (ref "C25") (pin "1") (pinfunction "1_1") (pintype "passive"))
      (node (ref "R24") (pin "2") (pinfunction "2_2") (pintype "passive"))
    )
    (net (code "17") (name "Net-(C38-Pad1)") (class "Default")
      (node (ref "C38") (pin "1") (pinfunction "1_1") (pintype "passive"))
      (node (ref "R29") (pin "1") (pinfunction "1_1") (pintype "passive"))
      (node (ref "R30") (pin "2") (pinfunction "2_2") (pintype "passive"))
    )
    (net (code "18") (name "Net-(CB2-Pad1)") (class "Default")
      (node (ref "CB2") (pin "1") (pinfunction "1_1") (pintype "passive"))
      (node (ref "CB3") (pin "1") (pinfunction "1_1") (pintype "passive"))
      (node (ref "L6") (pin "1") (pinfunction "1_1") (pintype "passive"))
      (node (ref "Q3") (pin "E") (pinfunction "E_E") (pintype "passive"))
      (node (ref "R11") (pin "2") (pinfunction "2_2") (pintype "passive"))
    )
    (net (code "19") (name "Net-(CB4-Pad1)") (class "Default")
      (node (ref "CB4") (pin "1") (pinfunction "1_1") (pintype "passive"))
      (node (ref "CB5") (pin "1") (pinfunction "1_1") (pintype "passive"))
      (node (ref "L4") (pin "2") (pinfunction "2_2") (pintype "passive"))
      (node (ref "Q1") (pin "E") (pinfunction "E_E") (pintype "passive"))
      (node (ref "R4") (pin "2") (pinfunction "2_2") (pintype "passive"))
    )
    (net (code "20") (name "Net-(CH7-2)") (class "Default")
      (node (ref "CH7") (pin "P$2") (pinfunction "2_P$2") (pintype "passive"))
      (node (ref "VGAIN") (pin "2") (pinfunction "2_2") (pintype "passive"))
    )
    (net (code "21") (name "Net-(CH7-3)") (class "Default")
      (node (ref "CH7") (pin "P$3") (pinfunction "3_P$3") (pintype "passive"))
      (node (ref "VGAIN") (pin "1") (pinfunction "1_1") (pintype "passive"))
    )
    (net (code "22") (name "Net-(CH7-4)") (class "Default")
      (node (ref "CH7") (pin "P$4") (pinfunction "4_P$4") (pintype "passive"))
      (node (ref "R30") (pin "1") (pinfunction "1_1") (pintype "passive"))
    )
    (net (code "23") (name "Net-(CH8-1)") (class "Default")
      (node (ref "CH8") (pin "P$1") (pinfunction "1_P$1") (pintype "passive"))
      (node (ref "TXSW") (pin "1") (pinfunction "1_1") (pintype "passive"))
    )
    (net (code "24") (name "Net-(CH8-3)") (class "Default")
      (node (ref "CH8") (pin "P$3") (pinfunction "3_P$3") (pintype "passive"))
      (node (ref "R1") (pin "2") (pinfunction "2_2") (pintype "passive"))
    )
    (net (code "25") (name "Net-(CH8-4)") (class "Default")
      (node (ref "CH8") (pin "P$4") (pinfunction "4_P$4") (pintype "passive"))
      (node (ref "TXSW") (pin "2") (pinfunction "2_2") (pintype "passive"))
    )
    (net (code "26") (name "Net-(CH9-1)") (class "Default")
      (node (ref "-VR") (pin "2") (pinfunction "2_2") (pintype "passive"))
      (node (ref "CH9") (pin "P$1") (pinfunction "1_P$1") (pintype "passive"))
    )
    (net (code "27") (name "Net-(CH9-3)") (class "Default")
      (node (ref "CH9") (pin "P$3") (pinfunction "3_P$3") (pintype "passive"))
      (node (ref "L5") (pin "1") (pinfunction "1_1") (pintype "passive"))
    )
    (net (code "28") (name "Net-(CH9-4)") (class "Default")
      (node (ref "-VR") (pin "1") (pinfunction "1_1") (pintype "passive"))
      (node (ref "CH9") (pin "P$4") (pinfunction "4_P$4") (pintype "passive"))
    )
    (net (code "29") (name "Net-(CH10-1)") (class "Default")
      (node (ref "CH10") (pin "P$1") (pinfunction "1_P$1") (pintype "passive"))
      (node (ref "RXSW") (pin "1") (pinfunction "1_1") (pintype "passive"))
    )
    (net (code "30") (name "Net-(CH10-3)") (class "Default")
      (node (ref "CH10") (pin "P$3") (pinfunction "3_P$3") (pintype "passive"))
      (node (ref "R8") (pin "2") (pinfunction "2_2") (pintype "passive"))
    )
    (net (code "31") (name "Net-(CH10-4)") (class "Default")
      (node (ref "CH10") (pin "P$4") (pinfunction "4_P$4") (pintype "passive"))
      (node (ref "RXSW") (pin "2") (pinfunction "2_2") (pintype "passive"))
    )
    (net (code "32") (name "Net-(CH11-1)") (class "Default")
      (node (ref "5VIN") (pin "2") (pinfunction "2_2") (pintype "passive"))
      (node (ref "CH11") (pin "P$1") (pinfunction "1_P$1") (pintype "passive"))
    )
    (net (code "33") (name "Net-(CH11-4)") (class "Default")
      (node (ref "5VIN") (pin "1") (pinfunction "1_1") (pintype "passive"))
      (node (ref "CH11") (pin "P$4") (pinfunction "4_P$4") (pintype "passive"))
    )
    (net (code "34") (name "Net-(D3-C)") (class "Default")
      (node (ref "C3") (pin "1") (pinfunction "1_1") (pintype "passive"))
      (node (ref "D3") (pin "K") (pinfunction "C_K") (pintype "passive"))
      (node (ref "L1") (pin "1") (pinfunction "1_1") (pintype "passive"))
      (node (ref "Q2") (pin "E") (pinfunction "E_E") (pintype "passive"))
    )
    (net (code "35") (name "Net-(D3-PadA)") (class "Default")
      (node (ref "D3") (pin "A") (pinfunction "A_A") (pintype "passive"))
      (node (ref "Q2") (pin "B") (pinfunction "B_B") (pintype "passive"))
      (node (ref "R5") (pin "1") (pinfunction "1_1") (pintype "passive"))
      (node (ref "R6") (pin "1") (pinfunction "1_1") (pintype "passive"))
      (node (ref "R7") (pin "2") (pinfunction "2_2") (pintype "passive"))
    )
    (net (code "36") (name "Net-(D4-C)") (class "Default")
      (node (ref "C4") (pin "1") (pinfunction "1_1") (pintype "passive"))
      (node (ref "D4") (pin "K") (pinfunction "C_K") (pintype "passive"))
      (node (ref "L3") (pin "1") (pinfunction "1_1") (pintype "passive"))
      (node (ref "Q5") (pin "E") (pinfunction "E_E") (pintype "passive"))
    )
    (net (code "37") (name "Net-(D4-PadA)") (class "Default")
      (node (ref "D4") (pin "A") (pinfunction "A_A") (pintype "passive"))
      (node (ref "Q5") (pin "B") (pinfunction "B_B") (pintype "passive"))
      (node (ref "R12") (pin "1") (pinfunction "1_1") (pintype "passive"))
      (node (ref "R13") (pin "1") (pinfunction "1_1") (pintype "passive"))
      (node (ref "R14") (pin "2") (pinfunction "2_2") (pintype "passive"))
    )
    (net (code "38") (name "Net-(D5-AC)") (class "Default")
      (node (ref "C26") (pin "2") (pinfunction "2_2") (pintype "passive"))
      (node (ref "C8") (pin "1") (pinfunction "1_1") (pintype "passive"))
      (node (ref "D5") (pin "3") (pinfunction "AC_3") (pintype "passive"))
    )
    (net (code "39") (name "Net-(L8-2)") (class "Default")
      (node (ref "CB8") (pin "1") (pinfunction "1_1") (pintype "passive"))
      (node (ref "L8") (pin "P$2") (pinfunction "2_P$2") (pintype "passive"))
      (node (ref "R15") (pin "2") (pinfunction "2_2") (pintype "passive"))
    )
    (net (code "40") (name "Net-(L9-1)") (class "Default")
      (node (ref "L9") (pin "P$1") (pinfunction "1_P$1") (pintype "passive"))
      (node (ref "R15") (pin "1") (pinfunction "1_1") (pintype "passive"))
    )
    (net (code "41") (name "Net-(L9-2)") (class "Default")
      (node (ref "C26") (pin "1") (pinfunction "1_1") (pintype "passive"))
      (node (ref "L9") (pin "P$2") (pinfunction "2_P$2") (pintype "passive"))
      (node (ref "LNA") (pin "P$3") (pinfunction "OUT_P$3") (pintype "output"))
    )
    (net (code "42") (name "Net-(POT1-E)") (class "Default")
      (node (ref "POT1") (pin "3") (pinfunction "E_3") (pintype "passive"))
      (node (ref "R26") (pin "1") (pinfunction "1_1") (pintype "passive"))
    )
    (net (code "43") (name "Net-(POT1-S)") (class "Default")
      (node (ref "C13") (pin "1") (pinfunction "1_1") (pintype "passive"))
      (node (ref "POT1") (pin "2") (pinfunction "S_2") (pintype "passive"))
      (node (ref "U1") (pin "10") (pinfunction "GAIN_10") (pintype "input"))
    )
    (net (code "44") (name "Net-(POT2-E)") (class "Default")
      (node (ref "POT2") (pin "3") (pinfunction "E_3") (pintype "passive"))
      (node (ref "R27") (pin "1") (pinfunction "1_1") (pintype "passive"))
    )
    (net (code "45") (name "Net-(POT2-S)") (class "Default")
      (node (ref "C23") (pin "1") (pinfunction "1_1") (pintype "passive"))
      (node (ref "POT2") (pin "2") (pinfunction "S_2") (pintype "passive"))
      (node (ref "R28") (pin "1") (pinfunction "1_1") (pintype "passive"))
      (node (ref "R29") (pin "2") (pinfunction "2_2") (pintype "passive"))
      (node (ref "U2") (pin "10") (pinfunction "GAIN_10") (pintype "input"))
    )
    (net (code "46") (name "Net-(Q1-PadB)") (class "Default")
      (node (ref "Q1") (pin "B") (pinfunction "B_B") (pintype "passive"))
      (node (ref "R3") (pin "2") (pinfunction "2_2") (pintype "passive"))
      (node (ref "R4") (pin "1") (pinfunction "1_1") (pintype "passive"))
    )
    (net (code "47") (name "Net-(Q1-PadC)") (class "Default")
      (node (ref "Q1") (pin "C") (pinfunction "C_C") (pintype "passive"))
      (node (ref "R5") (pin "2") (pinfunction "2_2") (pintype "passive"))
      (node (ref "R6") (pin "2") (pinfunction "2_2") (pintype "passive"))
    )
    (net (code "48") (name "Net-(Q3-PadB)") (class "Default")
      (node (ref "Q3") (pin "B") (pinfunction "B_B") (pintype "passive"))
      (node (ref "R10") (pin "2") (pinfunction "2_2") (pintype "passive"))
      (node (ref "R11") (pin "1") (pinfunction "1_1") (pintype "passive"))
    )
    (net (code "49") (name "Net-(Q3-PadC)") (class "Default")
      (node (ref "Q3") (pin "C") (pinfunction "C_C") (pintype "passive"))
      (node (ref "R12") (pin "2") (pinfunction "2_2") (pintype "passive"))
      (node (ref "R13") (pin "2") (pinfunction "2_2") (pintype "passive"))
    )
    (net (code "50") (name "Net-(Q4-D)") (class "Default")
      (node (ref "Q4") (pin "3") (pinfunction "D_3") (pintype "passive"))
      (node (ref "R10") (pin "1") (pinfunction "1_1") (pintype "passive"))
    )
    (net (code "51") (name "Net-(Q4-G)") (class "Default")
      (node (ref "C6") (pin "1") (pinfunction "1_1") (pintype "passive"))
      (node (ref "Q4") (pin "1") (pinfunction "G_1") (pintype "passive"))
      (node (ref "R8") (pin "1") (pinfunction "1_1") (pintype "passive"))
      (node (ref "R9") (pin "2") (pinfunction "2_2") (pintype "passive"))
    )
    (net (code "52") (name "Net-(Q6-D)") (class "Default")
      (node (ref "Q6") (pin "3") (pinfunction "D_3") (pintype "passive"))
      (node (ref "R3") (pin "1") (pinfunction "1_1") (pintype "passive"))
    )
    (net (code "53") (name "Net-(Q6-G)") (class "Default")
      (node (ref "C5") (pin "1") (pinfunction "1_1") (pintype "passive"))
      (node (ref "Q6") (pin "1") (pinfunction "G_1") (pintype "passive"))
      (node (ref "R1") (pin "1") (pinfunction "1_1") (pintype "passive"))
      (node (ref "R2") (pin "2") (pinfunction "2_2") (pintype "passive"))
    )
    (net (code "54") (name "Net-(T1-1)") (class "Default")
      (node (ref "R20") (pin "2") (pinfunction "2_2") (pintype "passive"))
      (node (ref "T1") (pin "P$1") (pinfunction "1_P$1") (pintype "passive"))
    )
    (net (code "55") (name "Net-(T1-6)") (class "Default")
      (node (ref "C15") (pin "2") (pinfunction "2_2") (pintype "passive"))
      (node (ref "T1") (pin "P$5") (pinfunction "6_P$5") (pintype "passive"))
    )
    (net (code "56") (name "Net-(T2-1)") (class "Default")
      (node (ref "R25") (pin "2") (pinfunction "2_2") (pintype "passive"))
      (node (ref "T2") (pin "P$1") (pinfunction "1_P$1") (pintype "passive"))
    )
    (net (code "57") (name "Net-(T2-4)") (class "Default")
      (node (ref "SJ2") (pin "2") (pinfunction "2_2") (pintype "passive"))
      (node (ref "T2") (pin "P$4") (pinfunction "4_P$4") (pintype "passive"))
    )
    (net (code "58") (name "Net-(T2-6)") (class "Default")
      (node (ref "C25") (pin "2") (pinfunction "2_2") (pintype "passive"))
      (node (ref "T2") (pin "P$5") (pinfunction "6_P$5") (pintype "passive"))
    )
    (net (code "59") (name "Net-(T3-P1)") (class "Default")
      (node (ref "RF_OUT") (pin "1") (pinfunction "1_1") (pintype "passive"))
      (node (ref "T3") (pin "P$3") (pinfunction "P1_P$3") (pintype "passive"))
    )
    (net (code "60") (name "Net-(T3-P2)") (class "Default")
      (node (ref "T3") (pin "P$4") (pinfunction "P2_P$4") (pintype "passive"))
      (node (ref "U$27") (pin "1") (pinfunction "1_1") (pintype "passive"))
    )
    (net (code "61") (name "Net-(T3-S)") (class "Default")
      (node (ref "SJ2") (pin "3") (pinfunction "3_3") (pintype "passive"))
      (node (ref "T3") (pin "P$1") (pinfunction "S_P$1") (pintype "passive"))
    )
    (net (code "62") (name "Net-(U1A-INH)") (class "Default")
      (node (ref "C8") (pin "2") (pinfunction "2_2") (pintype "passive"))
      (node (ref "C9") (pin "1") (pinfunction "1_1") (pintype "passive"))
      (node (ref "R16") (pin "2") (pinfunction "2_2") (pintype "passive"))
      (node (ref "U1") (pin "2") (pinfunction "INH_2") (pintype "input"))
    )
    (net (code "63") (name "Net-(U1A-LMD)") (class "Default")
      (node (ref "CB17") (pin "1") (pinfunction "1_1") (pintype "passive"))
      (node (ref "CB18") (pin "1") (pinfunction "1_1") (pintype "passive"))
      (node (ref "U1") (pin "1") (pinfunction "LMD_1") (pintype "passive"))
    )
    (net (code "64") (name "Net-(U1A-LON)") (class "Default")
      (node (ref "C10") (pin "2") (pinfunction "2_2") (pintype "passive"))
      (node (ref "C12") (pin "1") (pinfunction "1_1") (pintype "passive"))
      (node (ref "U1") (pin "4") (pinfunction "LON_4") (pintype "output"))
    )
    (net (code "65") (name "Net-(U1A-LOP)") (class "Default")
      (node (ref "C11") (pin "1") (pinfunction "1_1") (pintype "passive"))
      (node (ref "U1") (pin "5") (pinfunction "LOP_5") (pintype "output"))
    )
    (net (code "66") (name "Net-(U1A-VPSL)") (class "Default")
      (node (ref "CB15") (pin "1") (pinfunction "1_1") (pintype "passive"))
      (node (ref "CB16") (pin "1") (pinfunction "1_1") (pintype "passive"))
      (node (ref "FB1") (pin "2") (pinfunction "2_2") (pintype "passive"))
      (node (ref "U1") (pin "3") (pinfunction "VPSL_3") (pintype "power_in"))
    )
    (net (code "67") (name "Net-(U1B-HILO)") (class "Default")
      (node (ref "R17") (pin "2") (pinfunction "2_2") (pintype "passive"))
      (node (ref "U1") (pin "13") (pinfunction "HILO_13") (pintype "input"))
    )
    (net (code "68") (name "Net-(U1B-RCLMP)") (class "Default")
      (node (ref "C14") (pin "1") (pinfunction "1_1") (pintype "passive"))
      (node (ref "R18") (pin "1") (pinfunction "1_1") (pintype "passive"))
      (node (ref "U1") (pin "12") (pinfunction "RCLMP_12") (pintype "passive"))
    )
    (net (code "69") (name "Net-(U1B-VCM)") (class "Default")
      (node (ref "CB19") (pin "1") (pinfunction "1_1") (pintype "passive"))
      (node (ref "U1") (pin "11") (pinfunction "VCM_11") (pintype "passive"))
    )
    (net (code "70") (name "Net-(U1B-VIN)") (class "Default")
      (node (ref "C12") (pin "2") (pinfunction "2_2") (pintype "passive"))
      (node (ref "U1") (pin "8") (pinfunction "VIN_8") (pintype "input"))
    )
    (net (code "71") (name "Net-(U1B-VIP)") (class "Default")
      (node (ref "C11") (pin "2") (pinfunction "2_2") (pintype "passive"))
      (node (ref "U1") (pin "7") (pinfunction "VIP_7") (pintype "input"))
    )
    (net (code "72") (name "Net-(U1B-VOH)") (class "Default")
      (node (ref "R20") (pin "1") (pinfunction "1_1") (pintype "passive"))
      (node (ref "U1") (pin "15") (pinfunction "VOH_15") (pintype "output"))
    )
    (net (code "73") (name "Net-(U1B-VOL)") (class "Default")
      (node (ref "R19") (pin "1") (pinfunction "1_1") (pintype "passive"))
      (node (ref "U1") (pin "16") (pinfunction "VOL_16") (pintype "output"))
    )
    (net (code "74") (name "Net-(U1B-VPOS)") (class "Default")
      (node (ref "CB10") (pin "1") (pinfunction "1_1") (pintype "passive"))
      (node (ref "CB9") (pin "1") (pinfunction "1_1") (pintype "passive"))
      (node (ref "FB2") (pin "2") (pinfunction "2_2") (pintype "passive"))
      (node (ref "R17") (pin "1") (pinfunction "1_1") (pintype "passive"))
      (node (ref "U1") (pin "14") (pinfunction "VPOS_14") (pintype "power_in"))
    )
    (net (code "75") (name "Net-(U2A-INH)") (class "Default")
      (node (ref "C18") (pin "2") (pinfunction "2_2") (pintype "passive"))
      (node (ref "C19") (pin "1") (pinfunction "1_1") (pintype "passive"))
      (node (ref "R21") (pin "2") (pinfunction "2_2") (pintype "passive"))
      (node (ref "U2") (pin "2") (pinfunction "INH_2") (pintype "input"))
    )
    (net (code "76") (name "Net-(U2A-LMD)") (class "Default")
      (node (ref "CB20") (pin "1") (pinfunction "1_1") (pintype "passive"))
      (node (ref "CB21") (pin "1") (pinfunction "1_1") (pintype "passive"))
      (node (ref "U2") (pin "1") (pinfunction "LMD_1") (pintype "passive"))
    )
    (net (code "77") (name "Net-(U2A-LON)") (class "Default")
      (node (ref "C20") (pin "2") (pinfunction "2_2") (pintype "passive"))
      (node (ref "C22") (pin "1") (pinfunction "1_1") (pintype "passive"))
      (node (ref "U2") (pin "4") (pinfunction "LON_4") (pintype "output"))
    )
    (net (code "78") (name "Net-(U2A-LOP)") (class "Default")
      (node (ref "C21") (pin "1") (pinfunction "1_1") (pintype "passive"))
      (node (ref "U2") (pin "5") (pinfunction "LOP_5") (pintype "output"))
    )
    (net (code "79") (name "Net-(U2A-VPSL)") (class "Default")
      (node (ref "CB11") (pin "1") (pinfunction "1_1") (pintype "passive"))
      (node (ref "CB12") (pin "1") (pinfunction "1_1") (pintype "passive"))
      (node (ref "FB3") (pin "2") (pinfunction "2_2") (pintype "passive"))
      (node (ref "U2") (pin "3") (pinfunction "VPSL_3") (pintype "power_in"))
    )
    (net (code "80") (name "Net-(U2B-HILO)") (class "Default")
      (node (ref "R22") (pin "2") (pinfunction "2_2") (pintype "passive"))
      (node (ref "U2") (pin "13") (pinfunction "HILO_13") (pintype "input"))
    )
    (net (code "81") (name "Net-(U2B-RCLMP)") (class "Default")
      (node (ref "C24") (pin "1") (pinfunction "1_1") (pintype "passive"))
      (node (ref "R23") (pin "1") (pinfunction "1_1") (pintype "passive"))
      (node (ref "U2") (pin "12") (pinfunction "RCLMP_12") (pintype "passive"))
    )
    (net (code "82") (name "Net-(U2B-VCM)") (class "Default")
      (node (ref "CB22") (pin "1") (pinfunction "1_1") (pintype "passive"))
      (node (ref "U2") (pin "11") (pinfunction "VCM_11") (pintype "passive"))
    )
    (net (code "83") (name "Net-(U2B-VIN)") (class "Default")
      (node (ref "C22") (pin "2") (pinfunction "2_2") (pintype "passive"))
      (node (ref "U2") (pin "8") (pinfunction "VIN_8") (pintype "input"))
    )
    (net (code "84") (name "Net-(U2B-VIP)") (class "Default")
      (node (ref "C21") (pin "2") (pinfunction "2_2") (pintype "passive"))
      (node (ref "U2") (pin "7") (pinfunction "VIP_7") (pintype "input"))
    )
    (net (code "85") (name "Net-(U2B-VOH)") (class "Default")
      (node (ref "R25") (pin "1") (pinfunction "1_1") (pintype "passive"))
      (node (ref "U2") (pin "15") (pinfunction "VOH_15") (pintype "output"))
    )
    (net (code "86") (name "Net-(U2B-VOL)") (class "Default")
      (node (ref "R24") (pin "1") (pinfunction "1_1") (pintype "passive"))
      (node (ref "U2") (pin "16") (pinfunction "VOL_16") (pintype "output"))
    )
    (net (code "87") (name "Net-(U2B-VPOS)") (class "Default")
      (node (ref "CB13") (pin "1") (pinfunction "1_1") (pintype "passive"))
      (node (ref "CB14") (pin "1") (pinfunction "1_1") (pintype "passive"))
      (node (ref "FB4") (pin "2") (pinfunction "2_2") (pintype "passive"))
      (node (ref "R22") (pin "1") (pinfunction "1_1") (pintype "passive"))
      (node (ref "U2") (pin "14") (pinfunction "VPOS_14") (pintype "power_in"))
    )
    (net (code "88") (name "unconnected-(SJ2-Pad1)") (class "Default")
      (node (ref "SJ2") (pin "1") (pinfunction "1_1") (pintype "passive"))
    )
  )
)
